# POGO_adapter.net
KiCad netlist of a schematic drawn in Altium Designer
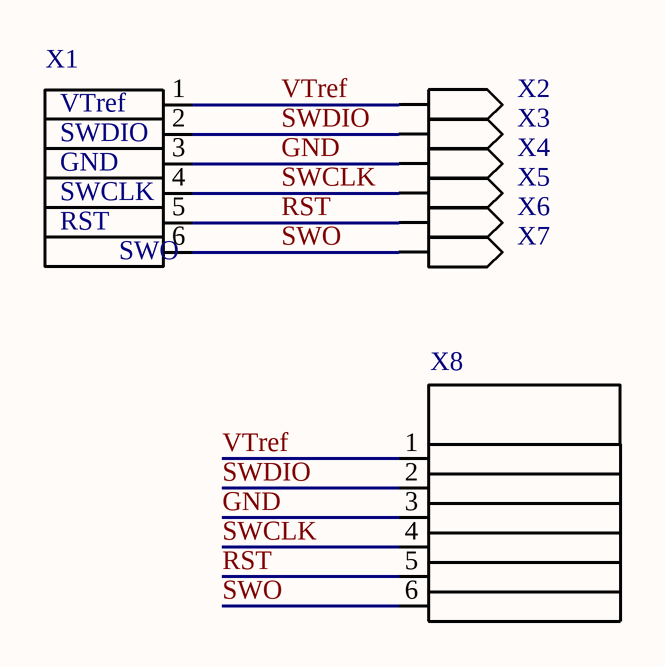
[diagram p0: POGO adapter.SchDoc]

(export (version "E")
  (design (tool "Eeschema 10.0.6"))
  (components
    (comp (ref "X1")
      (value "IDC10 edge")
      (footprint "BH-6 edge")
      (libsource (lib "POGO adapter") (part "IDC10 edge"))
    )
    (comp (ref "X2") (value "POGO") (footprint "POGO") (libsource (lib "POGO adapter") (part "POGO")))
    (comp (ref "X3") (value "POGO") (footprint "POGO") (libsource (lib "POGO adapter") (part "POGO")))
    (comp (ref "X4") (value "POGO") (footprint "POGO") (libsource (lib "POGO adapter") (part "POGO")))
    (comp (ref "X5") (value "POGO") (footprint "POGO") (libsource (lib "POGO adapter") (part "POGO")))
    (comp (ref "X6") (value "POGO") (footprint "POGO") (libsource (lib "POGO adapter") (part "POGO")))
    (comp (ref "X7") (value "POGO") (footprint "POGO") (libsource (lib "POGO adapter") (part "POGO")))
    (comp (ref "X8")
      (value "PLS-6R")
      (footprint "PLS-6R")
      (description "2.00 mm Single-Row Connector THM")
      (libsource (lib "POGO adapter") (part "PLS-6R"))
    )
  )
  (nets
    (net (code "1") (name "/GND") (class "Default")
      (node (ref "X1") (pin "3") (pinfunction "3_3") (pintype "passive"))
      (node (ref "X4") (pin "1") (pinfunction "1_1") (pintype "passive"))
      (node (ref "X8") (pin "3") (pintype "passive"))
    )
    (net (code "2") (name "/RST") (class "Default")
      (node (ref "X1") (pin "5") (pinfunction "5_5") (pintype "passive"))
      (node (ref "X6") (pin "1") (pinfunction "1_1") (pintype "passive"))
      (node (ref "X8") (pin "5") (pintype "passive"))
    )
    (net (code "3") (name "/SWCLK") (class "Default")
      (node (ref "X1") (pin "4") (pinfunction "4_4") (pintype "passive"))
      (node (ref "X5") (pin "1") (pinfunction "1_1") (pintype "passive"))
      (node (ref "X8") (pin "4") (pintype "passive"))
    )
    (net (code "4") (name "/SWDIO") (class "Default")
      (node (ref "X1") (pin "2") (pinfunction "2_2") (pintype "passive"))
      (node (ref "X3") (pin "1") (pinfunction "1_1") (pintype "passive"))
      (node (ref "X8") (pin "2") (pintype "passive"))
    )
    (net (code "5") (name "/SWO") (class "Default")
      (node (ref "X1") (pin "6") (pinfunction "6_6") (pintype "passive"))
      (node (ref "X7") (pin "1") (pinfunction "1_1") (pintype "passive"))
      (node (ref "X8") (pin "6") (pintype "passive"))
    )
    (net (code "6") (name "/VTref") (class "Default")
      (node (ref "X1") (pin "1") (pinfunction "1_1") (pintype "passive"))
      (node (ref "X2") (pin "1") (pinfunction "1_1") (pintype "passive"))
      (node (ref "X8") (pin "1") (pintype "passive"))
    )
  )
)
